# DS157-1_2-B.net
KiCad netlist of a schematic drawn in Altium Designer
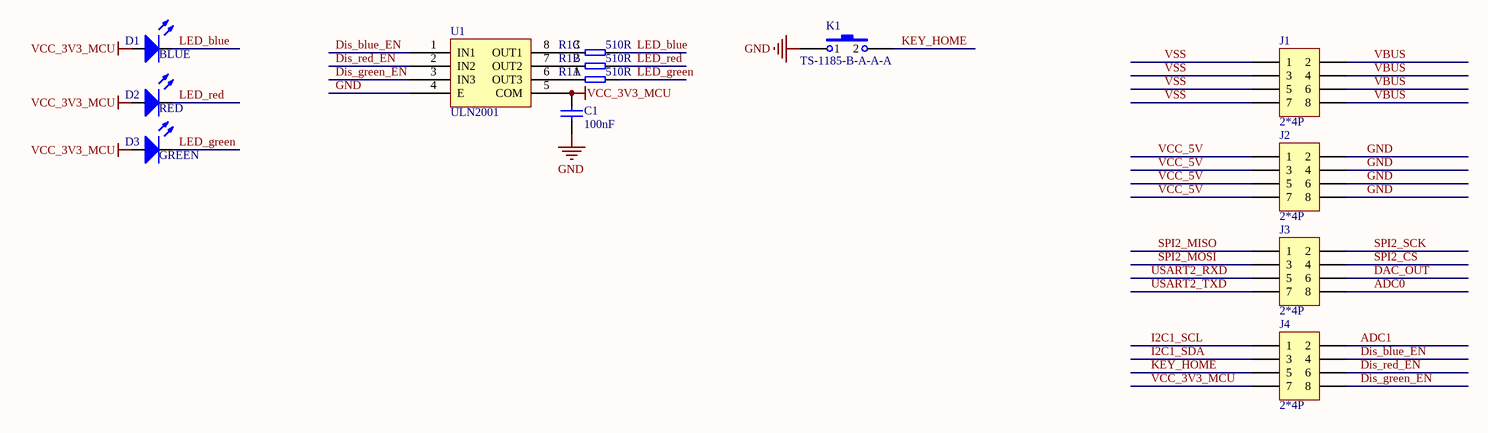
[diagram p0: DS157-1.2-B心率传感器.SchDoc]

(export (version "E")
  (design (tool "Eeschema 10.0.6"))
  (components
    (comp (ref "C1")
      (value "100nF")
      (footprint "0603CAP")
      (description "贴片电容")
      (fields (field (name "Comment") "SMDCAP00013"))
      (libsource (lib "AD_SCH") (part "MLCC 100nF 50V ±10％ 0603"))
    )
    (comp (ref "D1")
      (value "BLUE")
      (footprint "LED_0805")
      (description "贴片LED")
      (fields (field (name "Comment") "SMDLED00010"))
      (libsource (lib "AD_SCH") (part "Chip 蓝色LED 0805"))
    )
    (comp (ref "D2")
      (value "RED")
      (footprint "LED_0805")
      (description "贴片LED")
      (fields (field (name "Comment") "SMDLED00003"))
      (libsource (lib "AD_SCH") (part "Chip 红色LED 0805"))
    )
    (comp (ref "D3")
      (value "GREEN")
      (footprint "LED_0805")
      (description "贴片LED")
      (fields (field (name "Comment") "Chip 翠绿LED 0805"))
      (libsource (lib "AD_SCH") (part "Chip 翠绿LED 0805"))
    )
    (comp (ref "J1")
      (value "2*4P")
      (footprint "X1321WVS-2x04J-C40D53")
      (description "双排针2x4P 立贴 1.27mm")
      (fields (field (name "Comment") "X1321WVS-2x04J-C40D53"))
      (libsource (lib "AD_SCH") (part "X1321WVS-2x04J-C40D53"))
    )
    (comp (ref "J2")
      (value "2*4P")
      (footprint "X1321WVS-2x04J-C40D53")
      (description "双排针2x4P 立贴 1.27mm")
      (fields (field (name "Comment") "X1321WVS-2x04J-C40D53"))
      (libsource (lib "AD_SCH") (part "X1321WVS-2x04J-C40D53"))
    )
    (comp (ref "J3")
      (value "2*4P")
      (footprint "X1321WVS-2x04J-C40D53")
      (description "双排针2x4P 立贴 1.27mm")
      (fields (field (name "Comment") "X1321WVS-2x04J-C40D53"))
      (libsource (lib "AD_SCH") (part "X1321WVS-2x04J-C40D53"))
    )
    (comp (ref "J4")
      (value "2*4P")
      (footprint "X1321WVS-2x04J-C40D53")
      (description "双排针2x4P 立贴 1.27mm")
      (fields (field (name "Comment") "X1321WVS-2x04J-C40D53"))
      (libsource (lib "AD_SCH") (part "X1321WVS-2x04J-C40D53"))
    )
    (comp (ref "K1")
      (value "TS-1185-B-A-A-A")
      (footprint "KEY_TS-1185-x-A-A-A")
      (description "轻触开关")
      (libsource (lib "AD_SCH") (part "TS-1185-B-A-A-A"))
    )
    (comp (ref "R1")
      (value "510R")
      (footprint "0603RES_Pack4")
      (description "贴片排阻")
      (fields (field (name "Comment") "SMDRES05003"))
      (libsource (lib "AD_SCH") (part "Chip R*4 510R 1/16W ±5％ 0603"))
    )
    (comp (ref "U1")
      (value "ULN2001")
      (footprint "SO-8")
      (description "电机驱动芯片")
      (fields (field (name "Comment") "SMDIC000018"))
      (libsource (lib "AD_SCH") (part "ULN2001 SOP-8"))
    )
  )
  (nets
    (net (code "1") (name "/ADC0") (class "Default")
      (node (ref "J3") (pin "8") (pinfunction "8_8") (pintype "passive"))
    )
    (net (code "2") (name "/ADC1") (class "Default")
      (node (ref "J4") (pin "2") (pinfunction "2_2") (pintype "passive"))
    )
    (net (code "3") (name "/DAC_OUT") (class "Default")
      (node (ref "J3") (pin "6") (pinfunction "6_6") (pintype "passive"))
    )
    (net (code "4") (name "/Dis_blue_EN") (class "Default")
      (node (ref "J4") (pin "4") (pinfunction "4_4") (pintype "passive"))
      (node (ref "U1") (pin "1") (pinfunction "IN1_1") (pintype "passive"))
    )
    (net (code "5") (name "/Dis_green_EN") (class "Default")
      (node (ref "J4") (pin "8") (pinfunction "8_8") (pintype "passive"))
      (node (ref "U1") (pin "3") (pinfunction "IN3_3") (pintype "passive"))
    )
    (net (code "6") (name "/Dis_red_EN") (class "Default")
      (node (ref "J4") (pin "6") (pinfunction "6_6") (pintype "passive"))
      (node (ref "U1") (pin "2") (pinfunction "IN2_2") (pintype "passive"))
    )
    (net (code "7") (name "/I2C1_SCL") (class "Default")
      (node (ref "J4") (pin "1") (pinfunction "1_1") (pintype "passive"))
    )
    (net (code "8") (name "/I2C1_SDA") (class "Default")
      (node (ref "J4") (pin "3") (pinfunction "3_3") (pintype "passive"))
    )
    (net (code "9") (name "/KEY_HOME") (class "Default")
      (node (ref "J4") (pin "5") (pinfunction "5_5") (pintype "passive"))
      (node (ref "K1") (pin "2") (pinfunction "2_2") (pintype "passive"))
    )
    (net (code "10") (name "/LED_blue") (class "Default")
      (node (ref "D1") (pin "2") (pinfunction "K_2") (pintype "passive"))
      (node (ref "R1") (pin "6") (pinfunction "6_6") (pintype "passive"))
    )
    (net (code "11") (name "/LED_green") (class "Default")
      (node (ref "D3") (pin "2") (pinfunction "K_2") (pintype "passive"))
      (node (ref "R1") (pin "8") (pinfunction "8_8") (pintype "passive"))
    )
    (net (code "12") (name "/LED_red") (class "Default")
      (node (ref "D2") (pin "2") (pinfunction "K_2") (pintype "passive"))
      (node (ref "R1") (pin "7") (pinfunction "7_7") (pintype "passive"))
    )
    (net (code "13") (name "/SPI2_CS") (class "Default")
      (node (ref "J3") (pin "4") (pinfunction "4_4") (pintype "passive"))
    )
    (net (code "14") (name "/SPI2_MISO") (class "Default")
      (node (ref "J3") (pin "1") (pinfunction "1_1") (pintype "passive"))
    )
    (net (code "15") (name "/SPI2_MOSI") (class "Default")
      (node (ref "J3") (pin "3") (pinfunction "3_3") (pintype "passive"))
    )
    (net (code "16") (name "/SPI2_SCK") (class "Default")
      (node (ref "J3") (pin "2") (pinfunction "2_2") (pintype "passive"))
    )
    (net (code "17") (name "/USART2_RXD") (class "Default")
      (node (ref "J3") (pin "5") (pinfunction "5_5") (pintype "passive"))
    )
    (net (code "18") (name "/USART2_TXD") (class "Default")
      (node (ref "J3") (pin "7") (pinfunction "7_7") (pintype "passive"))
    )
    (net (code "19") (name "/VBUS") (class "Default")
      (node (ref "J1") (pin "2") (pinfunction "2_2") (pintype "passive"))
      (node (ref "J1") (pin "4") (pinfunction "4_4") (pintype "passive"))
      (node (ref "J1") (pin "6") (pinfunction "6_6") (pintype "passive"))
      (node (ref "J1") (pin "8") (pinfunction "8_8") (pintype "passive"))
    )
    (net (code "20") (name "/VCC_5V") (class "Default")
      (node (ref "J2") (pin "1") (pinfunction "1_1") (pintype "passive"))
      (node (ref "J2") (pin "3") (pinfunction "3_3") (pintype "passive"))
      (node (ref "J2") (pin "5") (pinfunction "5_5") (pintype "passive"))
      (node (ref "J2") (pin "7") (pinfunction "7_7") (pintype "passive"))
    )
    (net (code "21") (name "/VSS") (class "Default")
      (node (ref "J1") (pin "1") (pinfunction "1_1") (pintype "passive"))
      (node (ref "J1") (pin "3") (pinfunction "3_3") (pintype "passive"))
      (node (ref "J1") (pin "5") (pinfunction "5_5") (pintype "passive"))
      (node (ref "J1") (pin "7") (pinfunction "7_7") (pintype "passive"))
    )
    (net (code "22") (name "GND") (class "Default")
      (node (ref "C1") (pin "1") (pinfunction "1_1") (pintype "passive"))
      (node (ref "J2") (pin "2") (pinfunction "2_2") (pintype "passive"))
      (node (ref "J2") (pin "4") (pinfunction "4_4") (pintype "passive"))
      (node (ref "J2") (pin "6") (pinfunction "6_6") (pintype "passive"))
      (node (ref "J2") (pin "8") (pinfunction "8_8") (pintype "passive"))
      (node (ref "K1") (pin "1") (pinfunction "1_1") (pintype "passive"))
      (node (ref "U1") (pin "4") (pinfunction "E_4") (pintype "passive"))
    )
    (net (code "23") (name "Net-(U1-OUT1)") (class "Default")
      (node (ref "R1") (pin "3") (pinfunction "3_3") (pintype "passive"))
      (node (ref "U1") (pin "8") (pinfunction "OUT1_8") (pintype "passive"))
    )
    (net (code "24") (name "Net-(U1-OUT2)") (class "Default")
      (node (ref "R1") (pin "2") (pinfunction "2_2") (pintype "passive"))
      (node (ref "U1") (pin "7") (pinfunction "OUT2_7") (pintype "passive"))
    )
    (net (code "25") (name "Net-(U1-OUT3)") (class "Default")
      (node (ref "R1") (pin "1") (pinfunction "1_1") (pintype "passive"))
      (node (ref "U1") (pin "6") (pinfunction "OUT3_6") (pintype "passive"))
    )
    (net (code "26") (name "VCC_3V3_MCU") (class "Default")
      (node (ref "C1") (pin "2") (pinfunction "2_2") (pintype "passive"))
      (node (ref "D1") (pin "1") (pinfunction "A_1") (pintype "passive"))
      (node (ref "D2") (pin "1") (pinfunction "A_1") (pintype "passive"))
      (node (ref "D3") (pin "1") (pinfunction "A_1") (pintype "passive"))
      (node (ref "J4") (pin "7") (pinfunction "7_7") (pintype "passive"))
      (node (ref "U1") (pin "5") (pinfunction "COM_5") (pintype "passive"))
    )
  )
)
